# 04_Misc.net
KiCad netlist of a schematic drawn in Altium Designer
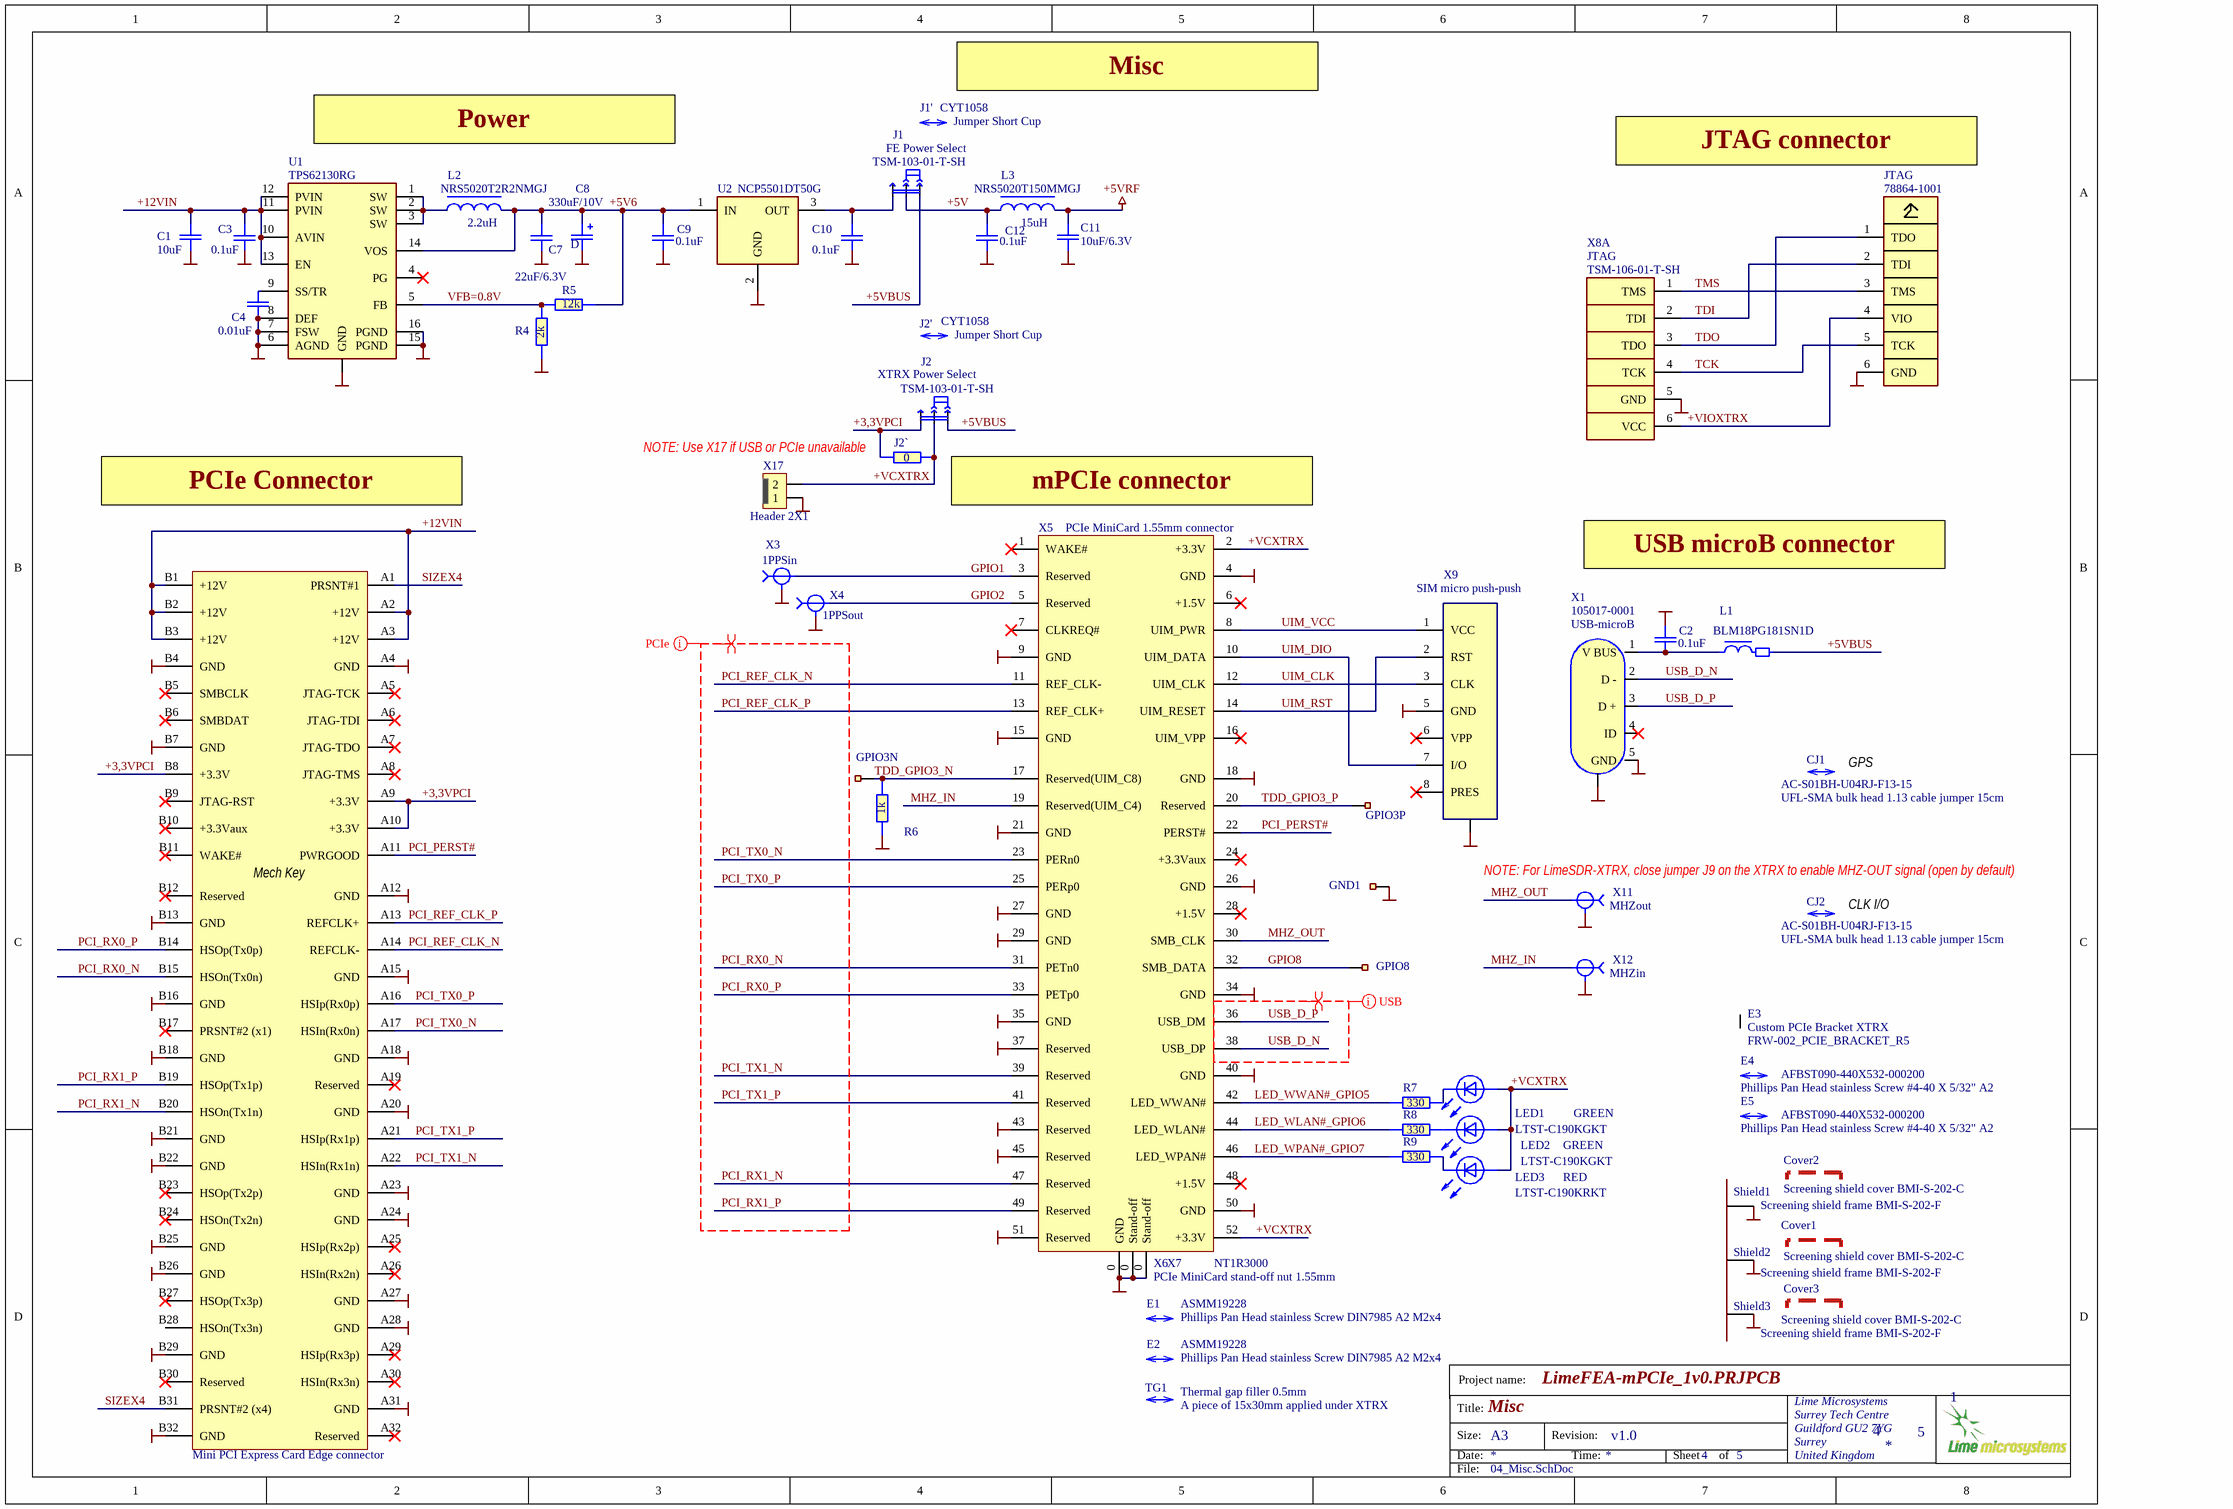
[diagram p0: 04_Misc.SchDoc]

(export (version "E")
  (design (tool "Eeschema 10.0.6"))
  (components
    (comp (ref "C1")
      (value "10uF")
      (footprint "C0805")
      (description "Capacitor")
      (fields (field (name "MANUFACTURER") "MURATA") (field (name "TOLERANCE") "20%"))
      (libsource (lib "Capacitors") (part "C0805"))
    )
    (comp (ref "C2")
      (value "0.1uF")
      (footprint "C0603-PHILLIPS")
      (description "Capacitor")
      (fields (field (name "MANUFACTURER") "MURATA") (field (name "TOLERANCE") "20%"))
      (libsource (lib "altium-import") (part "root_2_C0603_"))
    )
    (comp (ref "C3")
      (value "0.1uF")
      (footprint "C0603-PHILLIPS")
      (description "Capacitor")
      (fields (field (name "MANUFACTURER") "MURATA") (field (name "TOLERANCE") "20%"))
      (libsource (lib "altium-import") (part "root_2_C0603_"))
    )
    (comp (ref "C4")
      (value "0.01uF")
      (footprint "C0603-PHILLIPS")
      (description "Capacitor")
      (fields (field (name "MANUFACTURER") "MURATA") (field (name "TOLERANCE") "20%"))
      (libsource (lib "Capacitors") (part "C0603"))
    )
    (comp (ref "C7")
      (value "22uF/6.3V")
      (footprint "C0603-PHILLIPS")
      (description "Capacitor")
      (fields (field (name "MANUFACTURER") "MURATA") (field (name "TOLERANCE") "20%"))
      (libsource (lib "altium-import") (part "root_2_C0603_"))
    )
    (comp (ref "C8")
      (value "330uF/10V")
      (footprint "cd7343")
      (description "Capacitor")
      (fields (field (name "MANUFACTURER") "Kemet"))
      (libsource (lib "altium-import") (part "root_0_CD7343_"))
    )
    (comp (ref "C9")
      (value "0.1uF")
      (footprint "C0603-PHILLIPS")
      (description "Capacitor")
      (fields (field (name "MANUFACTURER") "MURATA") (field (name "TOLERANCE") "20%"))
      (libsource (lib "altium-import") (part "root_2_C0603_"))
    )
    (comp (ref "C10")
      (value "0.1uF")
      (footprint "C0603-PHILLIPS")
      (description "Capacitor")
      (fields (field (name "MANUFACTURER") "MURATA") (field (name "TOLERANCE") "20%"))
      (libsource (lib "altium-import") (part "root_2_C0603_"))
    )
    (comp (ref "C11")
      (value "10uF/6.3V")
      (footprint "C0603-Phillips")
      (description "Capacitor")
      (fields (field (name "MANUFACTURER") "MURATA") (field (name "TOLERANCE") "20%"))
      (libsource (lib "") (part "C0603_1"))
    )
    (comp (ref "C12")
      (value "0.1uF")
      (footprint "C0603-PHILLIPS")
      (description "Capacitor")
      (fields (field (name "MANUFACTURER") "MURATA") (field (name "TOLERANCE") "20%"))
      (libsource (lib "altium-import") (part "root_2_C0603_"))
    )
    (comp (ref "CJ1")
      (value "AC-S01BH-U04RJ-F13-15")
      (description "Cable jumper")
      (fields
        (field (name "MANUFACTURER") "RFSupplier")
        (field (name "MISC") "UFL-SMA bulk head 1.13 cable jumper 15cm")
      )
      (libsource (lib "LimeFEA-mPCIe_1v0") (part "Mating part"))
    )
    (comp (ref "CJ2")
      (value "AC-S01BH-U04RJ-F13-15")
      (description "Cable jumper")
      (fields
        (field (name "MANUFACTURER") "RFSupplier")
        (field (name "MISC") "UFL-SMA bulk head 1.13 cable jumper 15cm")
      )
      (libsource (lib "LimeFEA-mPCIe_1v0") (part "Mating part"))
    )
    (comp (ref "Cover1")
      (value "Screening shield cover BMI-S-202-C")
      (description "Screening shield cover")
      (fields (field (name "MANUFACTURER") "Laird Tech"))
      (libsource (lib "LimeFEA-mPCIe_1v0") (part "Screen cover BMI-S-202-C"))
    )
    (comp (ref "Cover2")
      (value "Screening shield cover BMI-S-202-C")
      (description "Screening shield cover")
      (fields (field (name "MANUFACTURER") "Laird Tech"))
      (libsource (lib "LimeFEA-mPCIe_1v0") (part "Screen cover BMI-S-202-C"))
    )
    (comp (ref "Cover3")
      (value "Screening shield cover BMI-S-202-C")
      (description "Screening shield cover")
      (fields (field (name "MANUFACTURER") "Laird Tech"))
      (libsource (lib "LimeFEA-mPCIe_1v0") (part "Screen cover BMI-S-202-C"))
    )
    (comp (ref "E1")
      (value "ASMM19228")
      (description "Screw M2")
      (fields
        (field (name "MANUFACTURER") "Aspen Fasteners")
        (field (name "MISC") "Phillips Pan Head stainless Screw DIN7985 A2 M2x4")
      )
      (libsource (lib "LimeFEA-mPCIe_1v0") (part "Mating subpart 1"))
    )
    (comp (ref "E2")
      (value "ASMM19228")
      (description "Screw M2")
      (fields
        (field (name "MANUFACTURER") "Aspen Fasteners")
        (field (name "MISC") "Phillips Pan Head stainless Screw DIN7985 A2 M2x4")
      )
      (libsource (lib "LimeFEA-mPCIe_1v0") (part "Mating subpart 1"))
    )
    (comp (ref "E3")
      (value "Custom PCIe Bracket XTRX")
      (footprint "Custom_PCIe_bracket_XTRX1")
      (description "CNC'ed enclosure component")
      (fields (field (name "ALTIUM_VALUE") "FRW-002_PCIE_BRACKET_R5"))
      (libsource (lib "LimeFEA-mPCIe_1v0") (part "PCI_Bracket_XTRX1"))
    )
    (comp (ref "E4")
      (value "AFBST090-440X532-000200")
      (description "Screw #4-40")
      (fields
        (field (name "MANUFACTURER") "Aspen Fasteners")
        (field (name "MISC") "Phillips Pan Head stainless Screw #4-40 X 5/32\" A2")
      )
      (libsource (lib "LimeFEA-mPCIe_1v0") (part "Mating subpart 1"))
    )
    (comp (ref "E5")
      (value "AFBST090-440X532-000200")
      (description "Screw #4-40")
      (fields
        (field (name "MANUFACTURER") "Aspen Fasteners")
        (field (name "MISC") "Phillips Pan Head stainless Screw #4-40 X 5/32\" A2")
      )
      (libsource (lib "LimeFEA-mPCIe_1v0") (part "Mating subpart 1"))
    )
    (comp (ref "GND1")
      (value "~")
      (footprint "KP-C_d1mm")
      (fields (field (name "MANUFACTURER") "PCB"))
      (libsource (lib "Connectors") (part "KP40X40"))
    )
    (comp (ref "GPIO3N")
      (value "~")
      (footprint "KP-C_d1mm")
      (fields (field (name "MANUFACTURER") "PCB"))
      (libsource (lib "Connectors") (part "KP40X40"))
    )
    (comp (ref "GPIO3P")
      (value "~")
      (footprint "KP-C_d1mm")
      (fields (field (name "MANUFACTURER") "PCB"))
      (libsource (lib "") (part "KP40X40_1"))
    )
    (comp (ref "GPIO8")
      (value "~")
      (footprint "KP-C_d1mm")
      (fields (field (name "MANUFACTURER") "PCB"))
      (libsource (lib "") (part "KP40X40_1"))
    )
    (comp (ref "J1")
      (value "TSM-103-01-T-SH")
      (footprint "Head_Male_3P_R/A_SMD")
      (description "Jumper 3 pin")
      (fields (field (name "MANUFACTURER") "Samtec") (field (name "ALTIUM_VALUE") "FE Power Select"))
      (libsource (lib "LimeFEA-mPCIe_1v0") (part "JUMPER_3P R/A SMD"))
    )
    (comp (ref "J1'")
      (value "CYT1058")
      (description "Jumper Short Cup")
      (fields (field (name "MISC") "Jumper Short Cup"))
      (libsource (lib "LimeFEA-mPCIe_1v0") (part "Mating part"))
    )
    (comp (ref "J2")
      (value "TSM-103-01-T-SH")
      (footprint "Head_Male_3P_R/A_SMD")
      (description "Jumper 3 pin")
      (fields (field (name "MANUFACTURER") "Samtec") (field (name "ALTIUM_VALUE") "XTRX Power Select"))
      (libsource (lib "LimeFEA-mPCIe_1v0") (part "JUMPER_3P R/A SMD"))
    )
    (comp (ref "J2'")
      (value "CYT1058")
      (description "Jumper Short Cup")
      (fields (field (name "MISC") "Jumper Short Cup"))
      (libsource (lib "Andy") (part "Mating part"))
    )
    (comp (ref "J2`")
      (value "0")
      (footprint "R0603-PHILLIPS")
      (description "Jumper")
      (fields (field (name "MANUFACTURER") "YAGEO") (field (name "TOLERANCE") "1%"))
      (libsource (lib "altium-import") (part "root_1_R0603_"))
    )
    (comp (ref "L1")
      (value "BLM18PG181SN1D")
      (footprint "TI160808-Phillips")
      (description "Ferrite Bead EMIFIL")
      (fields (field (name "MANUFACTURER") "MURATA"))
      (libsource (lib "LimeFEA-mPCIe_1v0") (part "EMI_BLM18"))
    )
    (comp (ref "L2")
      (value "2.2uH")
      (footprint "L-NRS5030")
      (description "Coil")
      (fields
        (field (name "MANUFACTURER") "Taiyo Yuden")
        (field (name "TOLERANCE") "20%")
        (field (name "NAME") "NRS5020T2R2NMGJ")
      )
      (libsource (lib "LimeFEA-mPCIe_1v0") (part "L-NRS50x0"))
    )
    (comp (ref "L3")
      (value "15uH")
      (footprint "L-NRS5030")
      (description "Coil")
      (fields
        (field (name "MANUFACTURER") "Taiyo Yuden")
        (field (name "TOLERANCE") "20%")
        (field (name "NAME") "NRS5020T150MMGJ")
      )
      (libsource (lib "LimeFEA-mPCIe_1v0") (part "L-NRS50x0"))
    )
    (comp (ref "LED1")
      (value "LTST-C190KGKT")
      (footprint "LED-0603GR")
      (description "LED GREEN")
      (fields (field (name "MANUFACTURER") "Lite-On Inc") (field (name "ALTIUM_VALUE") "GREEN"))
      (libsource (lib "LimeFEA-mPCIe_1v0") (part "LED0603GR_Lite-On"))
    )
    (comp (ref "LED2")
      (value "LTST-C190KGKT")
      (footprint "LED-0603GR")
      (description "LED GREEN")
      (fields (field (name "MANUFACTURER") "Lite-On Inc") (field (name "ALTIUM_VALUE") "GREEN"))
      (libsource (lib "LimeFEA-mPCIe_1v0") (part "LED0603GR_Lite-On"))
    )
    (comp (ref "LED3")
      (value "LTST-C190KRKT")
      (footprint "LED-0603RD")
      (description "LED RED")
      (fields (field (name "MANUFACTURER") "Lite-On Inc") (field (name "ALTIUM_VALUE") "RED"))
      (libsource (lib "LimeFEA-mPCIe_1v0") (part "LED0603RD_Lite-On"))
    )
    (comp (ref "R4")
      (value "2k")
      (footprint "R0603-PHILLIPS")
      (description "Resistor")
      (fields (field (name "MANUFACTURER") "YAGEO") (field (name "TOLERANCE") "1%"))
      (libsource (lib "Resistors") (part "R0603"))
    )
    (comp (ref "R5")
      (value "12k")
      (footprint "R0603-PHILLIPS")
      (description "Resistor")
      (fields (field (name "MANUFACTURER") "YAGEO") (field (name "TOLERANCE") "1%"))
      (libsource (lib "") (part "R0603_1"))
    )
    (comp (ref "R6")
      (value "1k")
      (footprint "R0603-PHILLIPS")
      (description "Resistor")
      (fields (field (name "MANUFACTURER") "YAGEO") (field (name "TOLERANCE") "1%"))
      (libsource (lib "altium-import") (part "root_2_R0603_"))
    )
    (comp (ref "R7")
      (value "330")
      (footprint "R0603-PHILLIPS")
      (description "Resistor")
      (fields (field (name "MANUFACTURER") "YAGEO") (field (name "TOLERANCE") "1%"))
      (libsource (lib "altium-import") (part "root_1_R0603_"))
    )
    (comp (ref "R8")
      (value "330")
      (footprint "R0603-PHILLIPS")
      (description "Resistor")
      (fields (field (name "MANUFACTURER") "YAGEO") (field (name "TOLERANCE") "1%"))
      (libsource (lib "altium-import") (part "root_1_R0603_"))
    )
    (comp (ref "R9")
      (value "330")
      (footprint "R0603-PHILLIPS")
      (description "Resistor")
      (fields (field (name "MANUFACTURER") "YAGEO") (field (name "TOLERANCE") "1%"))
      (libsource (lib "altium-import") (part "root_1_R0603_"))
    )
    (comp (ref "Shield1")
      (value "Screening shield frame BMI-S-202-F")
      (footprint "BMI-S-202-F")
      (description "Screening shield frame")
      (fields (field (name "MANUFACTURER") "Laird Tech"))
      (libsource (lib "LimeFEA-mPCIe_1v0") (part "Screen frame BMI-S-202-F"))
    )
    (comp (ref "Shield2")
      (value "Screening shield frame BMI-S-202-F")
      (footprint "BMI-S-202-F")
      (description "Screening shield frame")
      (fields (field (name "MANUFACTURER") "Laird Tech"))
      (libsource (lib "LimeFEA-mPCIe_1v0") (part "Screen frame BMI-S-202-F"))
    )
    (comp (ref "Shield3")
      (value "Screening shield frame BMI-S-202-F")
      (footprint "BMI-S-202-F")
      (description "Screening shield frame")
      (fields (field (name "MANUFACTURER") "Laird Tech"))
      (libsource (lib "LimeFEA-mPCIe_1v0") (part "Screen frame BMI-S-202-F"))
    )
    (comp (ref "TG1")
      (value "A piece of 15x30mm applied under XTRX")
      (description "Thermal gap filler")
      (fields (field (name "MANUFACTURER") "Wakefield") (field (name "MISC") "Thermal gap filler 0.5mm"))
      (libsource (lib "LimeFEA-mPCIe_1v0") (part "Mating subpart 1"))
    )
    (comp (ref "U1")
      (value "TPS62130RG")
      (footprint "QFN16(3x3/0/5mm)-Case485AE")
      (description "IC")
      (fields (field (name "MANUFACTURER") "TI"))
      (libsource (lib "LimeFEA-mPCIe_1v0") (part "TPS6213x"))
    )
    (comp (ref "U2")
      (value "NCP5501DT50G")
      (footprint "DPAK-3")
      (description "IC LDO fixed Vo")
      (fields (field (name "MANUFACTURER") "ON Semi"))
      (libsource (lib "LimeFEA-mPCIe_1v0") (part "NCP5501DTxxG"))
    )
    (comp (ref "X1")
      (value "105017-0001")
      (footprint "USB-micro-B")
      (description "Connector microUSB-B")
      (fields (field (name "MANUFACTURER") "MOLEX") (field (name "NAME") "USB-microB"))
      (libsource (lib "LimeFEA-mPCIe_1v0") (part "USB-microB_105017-1"))
    )
    (comp (ref "X2")
      (value "Mini PCI Express Card Edge connector")
      (footprint "PCIe x4 edge connector")
      (description "PCIe x4 Card edge connector")
      (libsource (lib "LimeFEA-mPCIe_1v0") (part "PCIe x4 Card"))
    )
    (comp (ref "X3")
      (value "0734120110")
      (footprint "U_FL")
      (description "Connector (UMCC)")
      (fields (field (name "MANUFACTURER") "Molex") (field (name "MISC") "1PPSin"))
      (libsource (lib "LimeFEA-mPCIe_1v0") (part "U_FL"))
    )
    (comp (ref "X4")
      (value "0734120110")
      (footprint "U_FL")
      (description "Connector (UMCC)")
      (fields (field (name "MANUFACTURER") "Molex") (field (name "MISC") "1PPSout"))
      (libsource (lib "LimeFEA-mPCIe_1v0") (part "U_FL"))
    )
    (comp (ref "X5")
      (value "PCIe MiniCard 1.55mm connector")
      (footprint "PCIe MiniCard 1.55mm conn")
      (description "Connector PCIe MiniCard")
      (fields (field (name "MANUFACTURER") "JAE Electronics"))
      (libsource (lib "LimeFEA-mPCIe_1v0") (part "PCIe MiniCard conn h1.55mm"))
    )
    (comp (ref "X6")
      (value "NT1R3000")
      (footprint "PCIe MiniCard 1.55mm stand off nut")
      (description "Stand-off nut PCIe MiniCard")
      (fields
        (field (name "MANUFACTURER") "JAE Electronics")
        (field (name "MISC") "PCIe MiniCard stand-off nut 1.55mm")
      )
      (libsource (lib "LimeFEA-mPCIe_1v0") (part "PCIe MiniCard nut h1.55mm"))
    )
    (comp (ref "X7")
      (value "NT1R3000")
      (footprint "PCIe MiniCard 1.55mm stand off nut")
      (description "Stand-off nut PCIe MiniCard")
      (fields (field (name "MANUFACTURER") "JAE Electronics"))
      (libsource (lib "LimeFEA-mPCIe_1v0") (part "PCIe MiniCard nut h1.55mm"))
    )
    (comp (ref "X8")
      (value "TSM-106-01-T-SH")
      (footprint "Head_Male_6P_R/A_SMD")
      (description "Connector header male")
      (fields (field (name "MANUFACTURER") "Samtec") (field (name "ALTIUM_VALUE") "JTAG"))
      (libsource (lib "LimeFEA-mPCIe_1v0") (part "Conn TSM-106-01-T-SH (=M20-89605)"))
    )
    (comp (ref "X9")
      (value "SIM micro push-push")
      (footprint "SIM_SF56S006V4BR2000-dig")
      (description "Connector SIM micro card")
      (fields (field (name "MANUFACTURER") "JAE"))
      (libsource (lib "LimeFEA-mPCIe_1v0") (part "SIM micro push-push"))
    )
    (comp (ref "X10")
      (value "JTAG")
      (footprint "Molex 78864-1001")
      (description "Connector board to board")
      (fields (field (name "MANUFACTURER") "Molex") (field (name "NAME") "78864-1001"))
      (libsource (lib "LimeFEA-mPCIe_1v0") (part "Conn Molex_788641001"))
    )
    (comp (ref "X11")
      (value "0734120110")
      (footprint "U_FL")
      (description "Connector (UMCC)")
      (fields (field (name "MANUFACTURER") "Molex") (field (name "MISC") "MHZout"))
      (libsource (lib "LimeFEA-mPCIe_1v0") (part "U_FL"))
    )
    (comp (ref "X12")
      (value "0734120110")
      (footprint "U_FL")
      (description "Connector (UMCC)")
      (fields (field (name "MANUFACTURER") "Molex") (field (name "MISC") "MHZin"))
      (libsource (lib "LimeFEA-mPCIe_1v0") (part "U_FL"))
    )
    (comp (ref "X17")
      (value "Header 2X1")
      (footprint "Header1x2_TH_LOCKING")
      (description "Headers & Wire Housings KK 100 Hdr FrLk Vert 02 Ckt Gold")
      (fields (field (name "MANUFACTURER PART NUMBER") "22-11-2026") (field (name "MANUFACTURER") "Molex"))
      (libsource (lib "LimeMicroAltiumLib_schLib_r04") (part "Header 2X1 LOCK"))
    )
  )
  (nets
    (net (code "1") (name "+5VRF") (class "Default")
      (node (ref "C11") (pin "2") (pinfunction "2_2") (pintype "passive"))
      (node (ref "L3") (pin "2") (pinfunction "2_2") (pintype "passive"))
    )
    (net (code "2") (name "/+3,3VPCI") (class "Default")
      (node (ref "J2") (pin "3") (pinfunction "3_3") (pintype "passive"))
      (node (ref "J2`") (pin "1") (pinfunction "1_1") (pintype "passive"))
      (node (ref "X2") (pin "A10") (pinfunction "+3.3V_A10") (pintype "passive"))
      (node (ref "X2") (pin "A9") (pinfunction "+3.3V_A9") (pintype "passive"))
      (node (ref "X2") (pin "B8") (pinfunction "+3.3V_B8") (pintype "passive"))
    )
    (net (code "3") (name "/+5V") (class "Default")
      (node (ref "C12") (pin "2") (pinfunction "2_2") (pintype "passive"))
      (node (ref "J1") (pin "2") (pinfunction "2_2") (pintype "passive"))
      (node (ref "L3") (pin "1") (pinfunction "1_1") (pintype "passive"))
    )
    (net (code "4") (name "/+5V6") (class "Default")
      (node (ref "C7") (pin "2") (pinfunction "2_2") (pintype "passive"))
      (node (ref "C8") (pin "1") (pinfunction "+_1") (pintype "passive"))
      (node (ref "C9") (pin "2") (pinfunction "2_2") (pintype "passive"))
      (node (ref "L2") (pin "2") (pinfunction "2_2") (pintype "passive"))
      (node (ref "R5") (pin "2") (pinfunction "2_2") (pintype "passive"))
      (node (ref "U1") (pin "14") (pinfunction "VOS_14") (pintype "passive"))
      (node (ref "U2") (pin "1") (pinfunction "IN_1") (pintype "passive"))
    )
    (net (code "5") (name "/+5VBUS") (class "Default")
      (node (ref "J1") (pin "1") (pinfunction "1_1") (pintype "passive"))
      (node (ref "J2") (pin "1") (pinfunction "1_1") (pintype "passive"))
      (node (ref "L1") (pin "2") (pinfunction "2_2") (pintype "passive"))
    )
    (net (code "6") (name "/+12VIN") (class "Default")
      (node (ref "C1") (pin "1") (pinfunction "1_1") (pintype "passive"))
      (node (ref "C3") (pin "2") (pinfunction "2_2") (pintype "passive"))
      (node (ref "U1") (pin "10") (pinfunction "AVIN_10") (pintype "passive"))
      (node (ref "U1") (pin "11") (pinfunction "PVIN_11") (pintype "passive"))
      (node (ref "U1") (pin "12") (pinfunction "PVIN_12") (pintype "passive"))
      (node (ref "U1") (pin "13") (pinfunction "EN_13") (pintype "passive"))
      (node (ref "X2") (pin "A2") (pinfunction "+12V_A2") (pintype "passive"))
      (node (ref "X2") (pin "A3") (pinfunction "+12V_A3") (pintype "passive"))
      (node (ref "X2") (pin "B1") (pinfunction "+12V_B1") (pintype "passive"))
      (node (ref "X2") (pin "B2") (pinfunction "+12V_B2") (pintype "passive"))
      (node (ref "X2") (pin "B3") (pinfunction "+12V_B3") (pintype "passive"))
    )
    (net (code "7") (name "/+VCXTRX") (class "Default")
      (node (ref "J2") (pin "2") (pinfunction "2_2") (pintype "passive"))
      (node (ref "J2`") (pin "2") (pinfunction "2_2") (pintype "passive"))
      (node (ref "LED1") (pin "2") (pinfunction "A_2") (pintype "passive"))
      (node (ref "LED2") (pin "2") (pinfunction "A_2") (pintype "passive"))
      (node (ref "LED3") (pin "2") (pinfunction "A_2") (pintype "passive"))
      (node (ref "X17") (pin "2") (pinfunction "2_2") (pintype "passive"))
      (node (ref "X5") (pin "2") (pinfunction "+3.3V_2") (pintype "passive"))
      (node (ref "X5") (pin "52") (pinfunction "+3.3V_52") (pintype "passive"))
    )
    (net (code "8") (name "/+VIOXTRX") (class "Default")
      (node (ref "X10") (pin "4") (pinfunction "VIO_4") (pintype "passive"))
      (node (ref "X8") (pin "6") (pinfunction "TMS_6") (pintype "passive"))
    )
    (net (code "9") (name "/GPIO1") (class "Default")
      (node (ref "X3") (pin "1") (pinfunction "1_1") (pintype "passive"))
      (node (ref "X5") (pin "3") (pinfunction "Reserved_3") (pintype "passive"))
    )
    (net (code "10") (name "/GPIO2") (class "Default")
      (node (ref "X4") (pin "1") (pinfunction "1_1") (pintype "passive"))
      (node (ref "X5") (pin "5") (pinfunction "Reserved_5") (pintype "passive"))
    )
    (net (code "11") (name "/GPIO8") (class "Default")
      (node (ref "GPIO8") (pin "1") (pinfunction "1_1") (pintype "passive"))
      (node (ref "X5") (pin "32") (pinfunction "SMB_DATA_32") (pintype "passive"))
    )
    (net (code "12") (name "/LED_WLAN#_GPIO6") (class "Default")
      (node (ref "R8") (pin "1") (pinfunction "1_1") (pintype "passive"))
      (node (ref "X5") (pin "44") (pinfunction "LED_WLAN#_44") (pintype "passive"))
    )
    (net (code "13") (name "/LED_WPAN#_GPIO7") (class "Default")
      (node (ref "R9") (pin "1") (pinfunction "1_1") (pintype "passive"))
      (node (ref "X5") (pin "46") (pinfunction "LED_WPAN#_46") (pintype "passive"))
    )
    (net (code "14") (name "/LED_WWAN#_GPIO5") (class "Default")
      (node (ref "R7") (pin "1") (pinfunction "1_1") (pintype "passive"))
      (node (ref "X5") (pin "42") (pinfunction "LED_WWAN#_42") (pintype "passive"))
    )
    (net (code "15") (name "/MHZ_IN") (class "Default")
      (node (ref "X12") (pin "1") (pinfunction "1_1") (pintype "passive"))
      (node (ref "X5") (pin "19") (pinfunction "Reserved(UIM_C4)_19") (pintype "passive"))
    )
    (net (code "16") (name "/MHZ_OUT") (class "Default")
      (node (ref "X11") (pin "1") (pinfunction "1_1") (pintype "passive"))
      (node (ref "X5") (pin "30") (pinfunction "SMB_CLK_30") (pintype "passive"))
    )
    (net (code "17") (name "/PCI_PERST#") (class "Default")
      (node (ref "X2") (pin "A11") (pinfunction "PWRGOOD_A11") (pintype "passive"))
      (node (ref "X5") (pin "22") (pinfunction "PERST#_22") (pintype "passive"))
    )
    (net (code "18") (name "/PCI_REF_CLK_N") (class "Default")
      (node (ref "X2") (pin "A14") (pinfunction "REFCLK-_A14") (pintype "passive"))
      (node (ref "X5") (pin "11") (pinfunction "REF_CLK-_11") (pintype "passive"))
    )
    (net (code "19") (name "/PCI_REF_CLK_P") (class "Default")
      (node (ref "X2") (pin "A13") (pinfunction "REFCLK+_A13") (pintype "passive"))
      (node (ref "X5") (pin "13") (pinfunction "REF_CLK+_13") (pintype "passive"))
    )
    (net (code "20") (name "/PCI_RX0_N") (class "Default")
      (node (ref "X2") (pin "B15") (pinfunction "HSOn(Tx0n)_B15") (pintype "passive"))
      (node (ref "X5") (pin "31") (pinfunction "PETn0_31") (pintype "passive"))
    )
    (net (code "21") (name "/PCI_RX0_P") (class "Default")
      (node (ref "X2") (pin "B14") (pinfunction "HSOp(Tx0p)_B14") (pintype "passive"))
      (node (ref "X5") (pin "33") (pinfunction "PETp0_33") (pintype "passive"))
    )
    (net (code "22") (name "/PCI_RX1_N") (class "Default")
      (node (ref "X2") (pin "B20") (pinfunction "HSOn(Tx1n)_B20") (pintype "passive"))
      (node (ref "X5") (pin "47") (pinfunction "Reserved_47") (pintype "passive"))
    )
    (net (code "23") (name "/PCI_RX1_P") (class "Default")
      (node (ref "X2") (pin "B19") (pinfunction "HSOp(Tx1p)_B19") (pintype "passive"))
      (node (ref "X5") (pin "49") (pinfunction "Reserved_49") (pintype "passive"))
    )
    (net (code "24") (name "/PCI_TX0_N") (class "Default")
      (node (ref "X2") (pin "A17") (pinfunction "HSIn(Rx0n)_A17") (pintype "passive"))
      (node (ref "X5") (pin "23") (pinfunction "PERn0_23") (pintype "passive"))
    )
    (net (code "25") (name "/PCI_TX0_P") (class "Default")
      (node (ref "X2") (pin "A16") (pinfunction "HSIp(Rx0p)_A16") (pintype "passive"))
      (node (ref "X5") (pin "25") (pinfunction "PERp0_25") (pintype "passive"))
    )
    (net (code "26") (name "/PCI_TX1_N") (class "Default")
      (node (ref "X2") (pin "A22") (pinfunction "HSIn(Rx1n)_A22") (pintype "passive"))
      (node (ref "X5") (pin "39") (pinfunction "Reserved_39") (pintype "passive"))
    )
    (net (code "27") (name "/PCI_TX1_P") (class "Default")
      (node (ref "X2") (pin "A21") (pinfunction "HSIp(Rx1p)_A21") (pintype "passive"))
      (node (ref "X5") (pin "41") (pinfunction "Reserved_41") (pintype "passive"))
    )
    (net (code "28") (name "/SIZEX4") (class "Default")
      (node (ref "X2") (pin "A1") (pinfunction "PRSNT#1_A1") (pintype "passive"))
      (node (ref "X2") (pin "B31") (pinfunction "PRSNT#2_(x4)_B31") (pintype "passive"))
    )
    (net (code "29") (name "/TCK") (class "Default")
      (node (ref "X10") (pin "5") (pinfunction "TCK_5") (pintype "passive"))
      (node (ref "X8") (pin "4") (pinfunction "TCK_4") (pintype "passive"))
    )
    (net (code "30") (name "/TDD_GPIO3_N") (class "Default")
      (node (ref "GPIO3N") (pin "1") (pinfunction "1_1") (pintype "passive"))
      (node (ref "R6") (pin "2") (pinfunction "2_2") (pintype "passive"))
      (node (ref "X5") (pin "17") (pinfunction "Reserved(UIM_C8)_17") (pintype "passive"))
    )
    (net (code "31") (name "/TDD_GPIO3_P") (class "Default")
      (node (ref "GPIO3P") (pin "1") (pinfunction "1_1") (pintype "passive"))
      (node (ref "X5") (pin "20") (pinfunction "Reserved_20") (pintype "passive"))
    )
    (net (code "32") (name "/TDI") (class "Default")
      (node (ref "X10") (pin "2") (pinfunction "TDI_2") (pintype "passive"))
      (node (ref "X8") (pin "2") (pinfunction "GND_2") (pintype "passive"))
    )
    (net (code "33") (name "/TDO") (class "Default")
      (node (ref "X10") (pin "1") (pinfunction "TDO_1") (pintype "passive"))
      (node (ref "X8") (pin "3") (pinfunction "TCK_3") (pintype "passive"))
    )
    (net (code "34") (name "/TMS") (class "Default")
      (node (ref "X10") (pin "3") (pinfunction "TMS_3") (pintype "passive"))
      (node (ref "X8") (pin "1") (pinfunction "VCC_1") (pintype "passive"))
    )
    (net (code "35") (name "/UIM_CLK") (class "Default")
      (node (ref "X5") (pin "12") (pinfunction "UIM_CLK_12") (pintype "passive"))
      (node (ref "X9") (pin "3") (pinfunction "CLK_3") (pintype "passive"))
    )
    (net (code "36") (name "/UIM_DIO") (class "Default")
      (node (ref "X5") (pin "10") (pinfunction "UIM_DATA_10") (pintype "passive"))
      (node (ref "X9") (pin "7") (pinfunction "I/O_7") (pintype "passive"))
    )
    (net (code "37") (name "/UIM_RST") (class "Default")
      (node (ref "X5") (pin "14") (pinfunction "UIM_RESET_14") (pintype "passive"))
      (node (ref "X9") (pin "2") (pinfunction "RST_2") (pintype "passive"))
    )
    (net (code "38") (name "/UIM_VCC") (class "Default")
      (node (ref "X5") (pin "8") (pinfunction "UIM_PWR_8") (pintype "passive"))
      (node (ref "X9") (pin "1") (pinfunction "VCC_1") (pintype "passive"))
    )
    (net (code "39") (name "/USB_D_N") (class "Default")
      (node (ref "X1") (pin "2") (pinfunction "D_-_2") (pintype "passive"))
      (node (ref "X5") (pin "38") (pinfunction "USB_DP_38") (pintype "passive"))
    )
    (net (code "40") (name "/USB_D_P") (class "Default")
      (node (ref "X1") (pin "3") (pinfunction "D_+_3") (pintype "passive"))
      (node (ref "X5") (pin "36") (pinfunction "USB_DM_36") (pintype "passive"))
    )
    (net (code "41") (name "GND") (class "Default")
      (node (ref "C1") (pin "2") (pinfunction "2_2") (pintype "passive"))
      (node (ref "C10") (pin "1") (pinfunction "1_1") (pintype "passive"))
      (node (ref "C11") (pin "1") (pinfunction "1_1") (pintype "passive"))
      (node (ref "C12") (pin "1") (pinfunction "1_1") (pintype "passive"))
      (node (ref "C2") (pin "2") (pinfunction "2_2") (pintype "passive"))
      (node (ref "C3") (pin "1") (pinfunction "1_1") (pintype "passive"))
      (node (ref "C4") (pin "2") (pinfunction "2_2") (pintype "passive"))
      (node (ref "C7") (pin "1") (pinfunction "1_1") (pintype "passive"))
      (node (ref "C8") (pin "2") (pinfunction "-_2") (pintype "passive"))
      (node (ref "C9") (pin "1") (pinfunction "1_1") (pintype "passive"))
      (node (ref "GND1") (pin "1") (pinfunction "1_1") (pintype "passive"))
      (node (ref "R4") (pin "2") (pinfunction "2_2") (pintype "passive"))
      (node (ref "R6") (pin "1") (pinfunction "1_1") (pintype "passive"))
      (node (ref "Shield1") (pin "0") (pinfunction "GND_0") (pintype "passive"))
      (node (ref "Shield2") (pin "0") (pinfunction "GND_0") (pintype "passive"))
      (node (ref "Shield3") (pin "0") (pinfunction "GND_0") (pintype "passive"))
      (node (ref "U1") (pin "0") (pinfunction "GND_0") (pintype "passive"))
      (node (ref "U1") (pin "15") (pinfunction "PGND_15") (pintype "passive"))
      (node (ref "U1") (pin "16") (pinfunction "PGND_16") (pintype "passive"))
      (node (ref "U1") (pin "6") (pinfunction "AGND_6") (pintype "passive"))
      (node (ref "U1") (pin "7") (pinfunction "FSW_7") (pintype "passive"))
      (node (ref "U1") (pin "8") (pinfunction "DEF_8") (pintype "passive"))
      (node (ref "U2") (pin "2") (pinfunction "GND_2") (pintype "passive"))
      (node (ref "X1") (pin "0") (pinfunction "GND_0") (pintype "passive"))
      (node (ref "X1") (pin "5") (pinfunction "GND_5") (pintype "passive"))
      (node (ref "X10") (pin "6") (pinfunction "GND_6") (pintype "passive"))
      (node (ref "X11") (pin "2") (pinfunction "GND_2") (pintype "passive"))
      (node (ref "X12") (pin "2") (pinfunction "GND_2") (pintype "passive"))
      (node (ref "X17") (pin "1") (pinfunction "1_1") (pintype "passive"))
      (node (ref "X2") (pin "A12") (pinfunction "GND_A12") (pintype "passive"))
      (node (ref "X2") (pin "A15") (pinfunction "GND_A15") (pintype "passive"))
      (node (ref "X2") (pin "A18") (pinfunction "GND_A18") (pintype "passive"))
      (node (ref "X2") (pin "A20") (pinfunction "GND_A20") (pintype "passive"))
      (node (ref "X2") (pin "A23") (pinfunction "GND_A23") (pintype "passive"))
      (node (ref "X2") (pin "A24") (pinfunction "GND_A24") (pintype "passive"))
      (node (ref "X2") (pin "A27") (pinfunction "GND_A27") (pintype "passive"))
      (node (ref "X2") (pin "A28") (pinfunction "GND_A28") (pintype "passive"))
      (node (ref "X2") (pin "A31") (pinfunction "GND_A31") (pintype "passive"))
      (node (ref "X2") (pin "A4") (pinfunction "GND_A4") (pintype "passive"))
      (node (ref "X2") (pin "B13") (pinfunction "GND_B13") (pintype "passive"))
      (node (ref "X2") (pin "B16") (pinfunction "GND_B16") (pintype "passive"))
      (node (ref "X2") (pin "B18") (pinfunction "GND_B18") (pintype "passive"))
      (node (ref "X2") (pin "B21") (pinfunction "GND_B21") (pintype "passive"))
      (node (ref "X2") (pin "B22") (pinfunction "GND_B22") (pintype "passive"))
      (node (ref "X2") (pin "B25") (pinfunction "GND_B25") (pintype "passive"))
      (node (ref "X2") (pin "B26") (pinfunction "GND_B26") (pintype "passive"))
      (node (ref "X2") (pin "B29") (pinfunction "GND_B29") (pintype "passive"))
      (node (ref "X2") (pin "B32") (pinfunction "GND_B32") (pintype "passive"))
      (node (ref "X2") (pin "B4") (pinfunction "GND_B4") (pintype "passive"))
      (node (ref "X2") (pin "B7") (pinfunction "GND_B7") (pintype "passive"))
      (node (ref "X3") (pin "2") (pinfunction "GND_2") (pintype "passive"))
      (node (ref "X4") (pin "2") (pinfunction "GND_2") (pintype "passive"))
      (node (ref "X5") (pin "0") (pinfunction "GND_0") (pintype "passive"))
      (node (ref "X5") (pin "15") (pinfunction "GND_15") (pintype "passive"))
      (node (ref "X5") (pin "18") (pinfunction "GND_18") (pintype "passive"))
      (node (ref "X5") (pin "21") (pinfunction "GND_21") (pintype "passive"))
      (node (ref "X5") (pin "26") (pinfunction "GND_26") (pintype "passive"))
      (node (ref "X5") (pin "27") (pinfunction "GND_27") (pintype "passive"))
      (node (ref "X5") (pin "29") (pinfunction "GND_29") (pintype "passive"))
      (node (ref "X5") (pin "34") (pinfunction "GND_34") (pintype "passive"))
      (node (ref "X5") (pin "35") (pinfunction "GND_35") (pintype "passive"))
      (node (ref "X5") (pin "37") (pinfunction "Reserved_37") (pintype "passive"))
      (node (ref "X5") (pin "4") (pinfunction "GND_4") (pintype "passive"))
      (node (ref "X5") (pin "40") (pinfunction "GND_40") (pintype "passive"))
      (node (ref "X5") (pin "43") (pinfunction "Reserved_43") (pintype "passive"))
      (node (ref "X5") (pin "45") (pinfunction "Reserved_45") (pintype "passive"))
      (node (ref "X5") (pin "50") (pinfunction "GND_50") (pintype "passive"))
      (node (ref "X5") (pin "51") (pinfunction "Reserved_51") (pintype "passive"))
      (node (ref "X5") (pin "9") (pinfunction "GND_9") (pintype "passive"))
      (node (ref "X6") (pin "0") (pinfunction "Stand-off_0") (pintype "passive"))
      (node (ref "X7") (pin "0") (pinfunction "Stand-off_0") (pintype "passive"))
      (node (ref "X8") (pin "5") (pinfunction "TDI_5") (pintype "passive"))
      (node (ref "X9") (pin "0") (pinfunction "GND_0") (pintype "passive"))
      (node (ref "X9") (pin "5") (pinfunction "GND_5") (pintype "passive"))
    )
    (net (code "42") (name "Net-(L2-Pad1)") (class "Default")
      (node (ref "L2") (pin "1") (pinfunction "1_1") (pintype "passive"))
      (node (ref "U1") (pin "1") (pinfunction "SW_1") (pintype "passive"))
      (node (ref "U1") (pin "2") (pinfunction "SW_2") (pintype "passive"))
      (node (ref "U1") (pin "3") (pinfunction "SW_3") (pintype "passive"))
    )
    (net (code "43") (name "Net-(LED1-K)") (class "Default")
      (node (ref "LED1") (pin "1") (pinfunction "K_1") (pintype "passive"))
      (node (ref "R7") (pin "2") (pinfunction "2_2") (pintype "passive"))
    )
    (net (code "44") (name "Net-(LED2-K)") (class "Default")
      (node (ref "LED2") (pin "1") (pinfunction "K_1") (pintype "passive"))
      (node (ref "R8") (pin "2") (pinfunction "2_2") (pintype "passive"))
    )
    (net (code "45") (name "Net-(LED3-K)") (class "Default")
      (node (ref "LED3") (pin "1") (pinfunction "K_1") (pintype "passive"))
      (node (ref "R9") (pin "2") (pinfunction "2_2") (pintype "passive"))
    )
    (net (code "46") (name "Net-(U1-FB)") (class "Default")
      (node (ref "R4") (pin "1") (pinfunction "1_1") (pintype "passive"))
      (node (ref "R5") (pin "1") (pinfunction "1_1") (pintype "passive"))
      (node (ref "U1") (pin "5") (pinfunction "FB_5") (pintype "passive"))
    )
    (net (code "47") (name "Net-(U1-SS{slash}TR)") (class "Default")
      (node (ref "C4") (pin "1") (pinfunction "1_1") (pintype "passive"))
      (node (ref "U1") (pin "9") (pinfunction "SS/TR_9") (pintype "passive"))
    )
    (net (code "48") (name "Net-(U2-OUT)") (class "Default")
      (node (ref "C10") (pin "2") (pinfunction "2_2") (pintype "passive"))
      (node (ref "J1") (pin "3") (pinfunction "3_3") (pintype "passive"))
      (node (ref "U2") (pin "3") (pinfunction "OUT_3") (pintype "passive"))
    )
    (net (code "49") (name "Net-(X1-V_BUS)") (class "Default")
      (node (ref "C2") (pin "1") (pinfunction "1_1") (pintype "passive"))
      (node (ref "L1") (pin "1") (pinfunction "1_1") (pintype "passive"))
      (node (ref "X1") (pin "1") (pinfunction "V_BUS_1") (pintype "power_in"))
    )
    (net (code "50") (name "unconnected-(CJ1-Pad)") (class "Default")
      (node (ref "CJ1") (pin "") (pintype "passive"))
    )
    (net (code "51") (name "unconnected-(CJ2-Pad)") (class "Default")
      (node (ref "CJ2") (pin "") (pintype "passive"))
    )
    (net (code "52") (name "unconnected-(E1-Pad)") (class "Default")
      (node (ref "E1") (pin "") (pintype "passive"))
    )
    (net (code "53") (name "unconnected-(E2-Pad)") (class "Default")
      (node (ref "E2") (pin "") (pintype "passive"))
    )
    (net (code "54") (name "unconnected-(E3-Pad0)") (class "Default")
      (node (ref "E3") (pin "0") (pinfunction "0_0") (pintype "passive"))
    )
    (net (code "55") (name "unconnected-(E4-Pad)") (class "Default")
      (node (ref "E4") (pin "") (pintype "passive"))
    )
    (net (code "56") (name "unconnected-(E5-Pad)") (class "Default")
      (node (ref "E5") (pin "") (pintype "passive"))
    )
    (net (code "57") (name "unconnected-(J1'-Pad)") (class "Default")
      (node (ref "J1'") (pin "") (pintype "passive"))
    )
    (net (code "58") (name "unconnected-(J2'-Pad)") (class "Default")
      (node (ref "J2'") (pin "") (pintype "passive"))
    )
    (net (code "59") (name "unconnected-(TG1-Pad)") (class "Default")
      (node (ref "TG1") (pin "") (pintype "passive"))
    )
    (net (code "60") (name "unconnected-(U1-PG-Pad4)") (class "Default")
      (node (ref "U1") (pin "4") (pinfunction "PG_4") (pintype "passive+no_connect"))
    )
    (net (code "61") (name "unconnected-(X1-ID-Pad4)") (class "Default")
      (node (ref "X1") (pin "4") (pinfunction "ID_4") (pintype "passive+no_connect"))
    )
    (net (code "62") (name "unconnected-(X2-+3.3Vaux-PadB10)") (class "Default")
      (node (ref "X2") (pin "B10") (pinfunction "+3.3Vaux_B10") (pintype "passive+no_connect"))
    )
    (net (code "63") (name "unconnected-(X2-HSIn(Rx2n)-PadA26)") (class "Default")
      (node (ref "X2") (pin "A26") (pinfunction "HSIn(Rx2n)_A26") (pintype "passive+no_connect"))
    )
    (net (code "64") (name "unconnected-(X2-HSIn(Rx3n)-PadA30)") (class "Default")
      (node (ref "X2") (pin "A30") (pinfunction "HSIn(Rx3n)_A30") (pintype "passive+no_connect"))
    )
    (net (code "65") (name "unconnected-(X2-HSIp(Rx2p)-PadA25)") (class "Default")
      (node (ref "X2") (pin "A25") (pinfunction "HSIp(Rx2p)_A25") (pintype "passive+no_connect"))
    )
    (net (code "66") (name "unconnected-(X2-HSIp(Rx3p)-PadA29)") (class "Default")
      (node (ref "X2") (pin "A29") (pinfunction "HSIp(Rx3p)_A29") (pintype "passive+no_connect"))
    )
    (net (code "67") (name "unconnected-(X2-HSOn(Tx2n)-PadB24)") (class "Default")
      (node (ref "X2") (pin "B24") (pinfunction "HSOn(Tx2n)_B24") (pintype "passive+no_connect"))
    )
    (net (code "68") (name "unconnected-(X2-HSOn(Tx3n)-PadB28)") (class "Default")
      (node (ref "X2") (pin "B28") (pinfunction "HSOn(Tx3n)_B28") (pintype "passive"))
    )
    (net (code "69") (name "unconnected-(X2-HSOp(Tx2p)-PadB23)") (class "Default")
      (node (ref "X2") (pin "B23") (pinfunction "HSOp(Tx2p)_B23") (pintype "passive+no_connect"))
    )
    (net (code "70") (name "unconnected-(X2-HSOp(Tx3p)-PadB27)") (class "Default")
      (node (ref "X2") (pin "B27") (pinfunction "HSOp(Tx3p)_B27") (pintype "passive+no_connect"))
    )
    (net (code "71") (name "unconnected-(X2-JTAG-RST-PadB9)") (class "Default")
      (node (ref "X2") (pin "B9") (pinfunction "JTAG-RST_B9") (pintype "passive+no_connect"))
    )
    (net (code "72") (name "unconnected-(X2-JTAG-TCK-PadA5)") (class "Default")
      (node (ref "X2") (pin "A5") (pinfunction "JTAG-TCK_A5") (pintype "passive+no_connect"))
    )
    (net (code "73") (name "unconnected-(X2-JTAG-TDI-PadA6)") (class "Default")
      (node (ref "X2") (pin "A6") (pinfunction "JTAG-TDI_A6") (pintype "passive+no_connect"))
    )
    (net (code "74") (name "unconnected-(X2-JTAG-TDO-PadA7)") (class "Default")
      (node (ref "X2") (pin "A7") (pinfunction "JTAG-TDO_A7") (pintype "passive+no_connect"))
    )
    (net (code "75") (name "unconnected-(X2-JTAG-TMS-PadA8)") (class "Default")
      (node (ref "X2") (pin "A8") (pinfunction "JTAG-TMS_A8") (pintype "passive+no_connect"))
    )
    (net (code "76") (name "unconnected-(X2-PRSNT#2_(x1)-PadB17)") (class "Default")
      (node (ref "X2") (pin "B17") (pinfunction "PRSNT#2_(x1)_B17") (pintype "passive+no_connect"))
    )
    (net (code "77") (name "unconnected-(X2-Reserved-PadA19)") (class "Default")
      (node (ref "X2") (pin "A19") (pinfunction "Reserved_A19") (pintype "passive+no_connect"))
    )
    (net (code "78") (name "unconnected-(X2-Reserved-PadA32)") (class "Default")
      (node (ref "X2") (pin "A32") (pinfunction "Reserved_A32") (pintype "passive+no_connect"))
    )
    (net (code "79") (name "unconnected-(X2-Reserved-PadB12)") (class "Default")
      (node (ref "X2") (pin "B12") (pinfunction "Reserved_B12") (pintype "passive+no_connect"))
    )
    (net (code "80") (name "unconnected-(X2-Reserved-PadB30)") (class "Default")
      (node (ref "X2") (pin "B30") (pinfunction "Reserved_B30") (pintype "passive+no_connect"))
    )
    (net (code "81") (name "unconnected-(X2-SMBCLK-PadB5)") (class "Default")
      (node (ref "X2") (pin "B5") (pinfunction "SMBCLK_B5") (pintype "passive+no_connect"))
    )
    (net (code "82") (name "unconnected-(X2-SMBDAT-PadB6)") (class "Default")
      (node (ref "X2") (pin "B6") (pinfunction "SMBDAT_B6") (pintype "passive+no_connect"))
    )
    (net (code "83") (name "unconnected-(X2-WAKE#-PadB11)") (class "Default")
      (node (ref "X2") (pin "B11") (pinfunction "WAKE#_B11") (pintype "passive+no_connect"))
    )
    (net (code "84") (name "unconnected-(X5-+1.5V-Pad6)") (class "Default")
      (node (ref "X5") (pin "6") (pinfunction "+1.5V_6") (pintype "passive+no_connect"))
    )
    (net (code "85") (name "unconnected-(X5-+1.5V-Pad28)") (class "Default")
      (node (ref "X5") (pin "28") (pinfunction "+1.5V_28") (pintype "passive+no_connect"))
    )
    (net (code "86") (name "unconnected-(X5-+1.5V-Pad48)") (class "Default")
      (node (ref "X5") (pin "48") (pinfunction "+1.5V_48") (pintype "passive+no_connect"))
    )
    (net (code "87") (name "unconnected-(X5-+3.3Vaux-Pad24)") (class "Default")
      (node (ref "X5") (pin "24") (pinfunction "+3.3Vaux_24") (pintype "passive+no_connect"))
    )
    (net (code "88") (name "unconnected-(X5-CLKREQ#-Pad7)") (class "Default")
      (node (ref "X5") (pin "7") (pinfunction "CLKREQ#_7") (pintype "passive+no_connect"))
    )
    (net (code "89") (name "unconnected-(X5-UIM_VPP-Pad16)") (class "Default")
      (node (ref "X5") (pin "16") (pinfunction "UIM_VPP_16") (pintype "passive+no_connect"))
    )
    (net (code "90") (name "unconnected-(X5-WAKE#-Pad1)") (class "Default")
      (node (ref "X5") (pin "1") (pinfunction "WAKE#_1") (pintype "passive+no_connect"))
    )
    (net (code "91") (name "unconnected-(X9-PRES-Pad8)") (class "Default")
      (node (ref "X9") (pin "8") (pinfunction "PRES_8") (pintype "passive+no_connect"))
    )
    (net (code "92") (name "unconnected-(X9-VPP-Pad6)") (class "Default")
      (node (ref "X9") (pin "6") (pinfunction "VPP_6") (pintype "passive+no_connect"))
    )
  )
)
